# HeadphoneOut.net
KiCad netlist of a schematic drawn in EAGLE
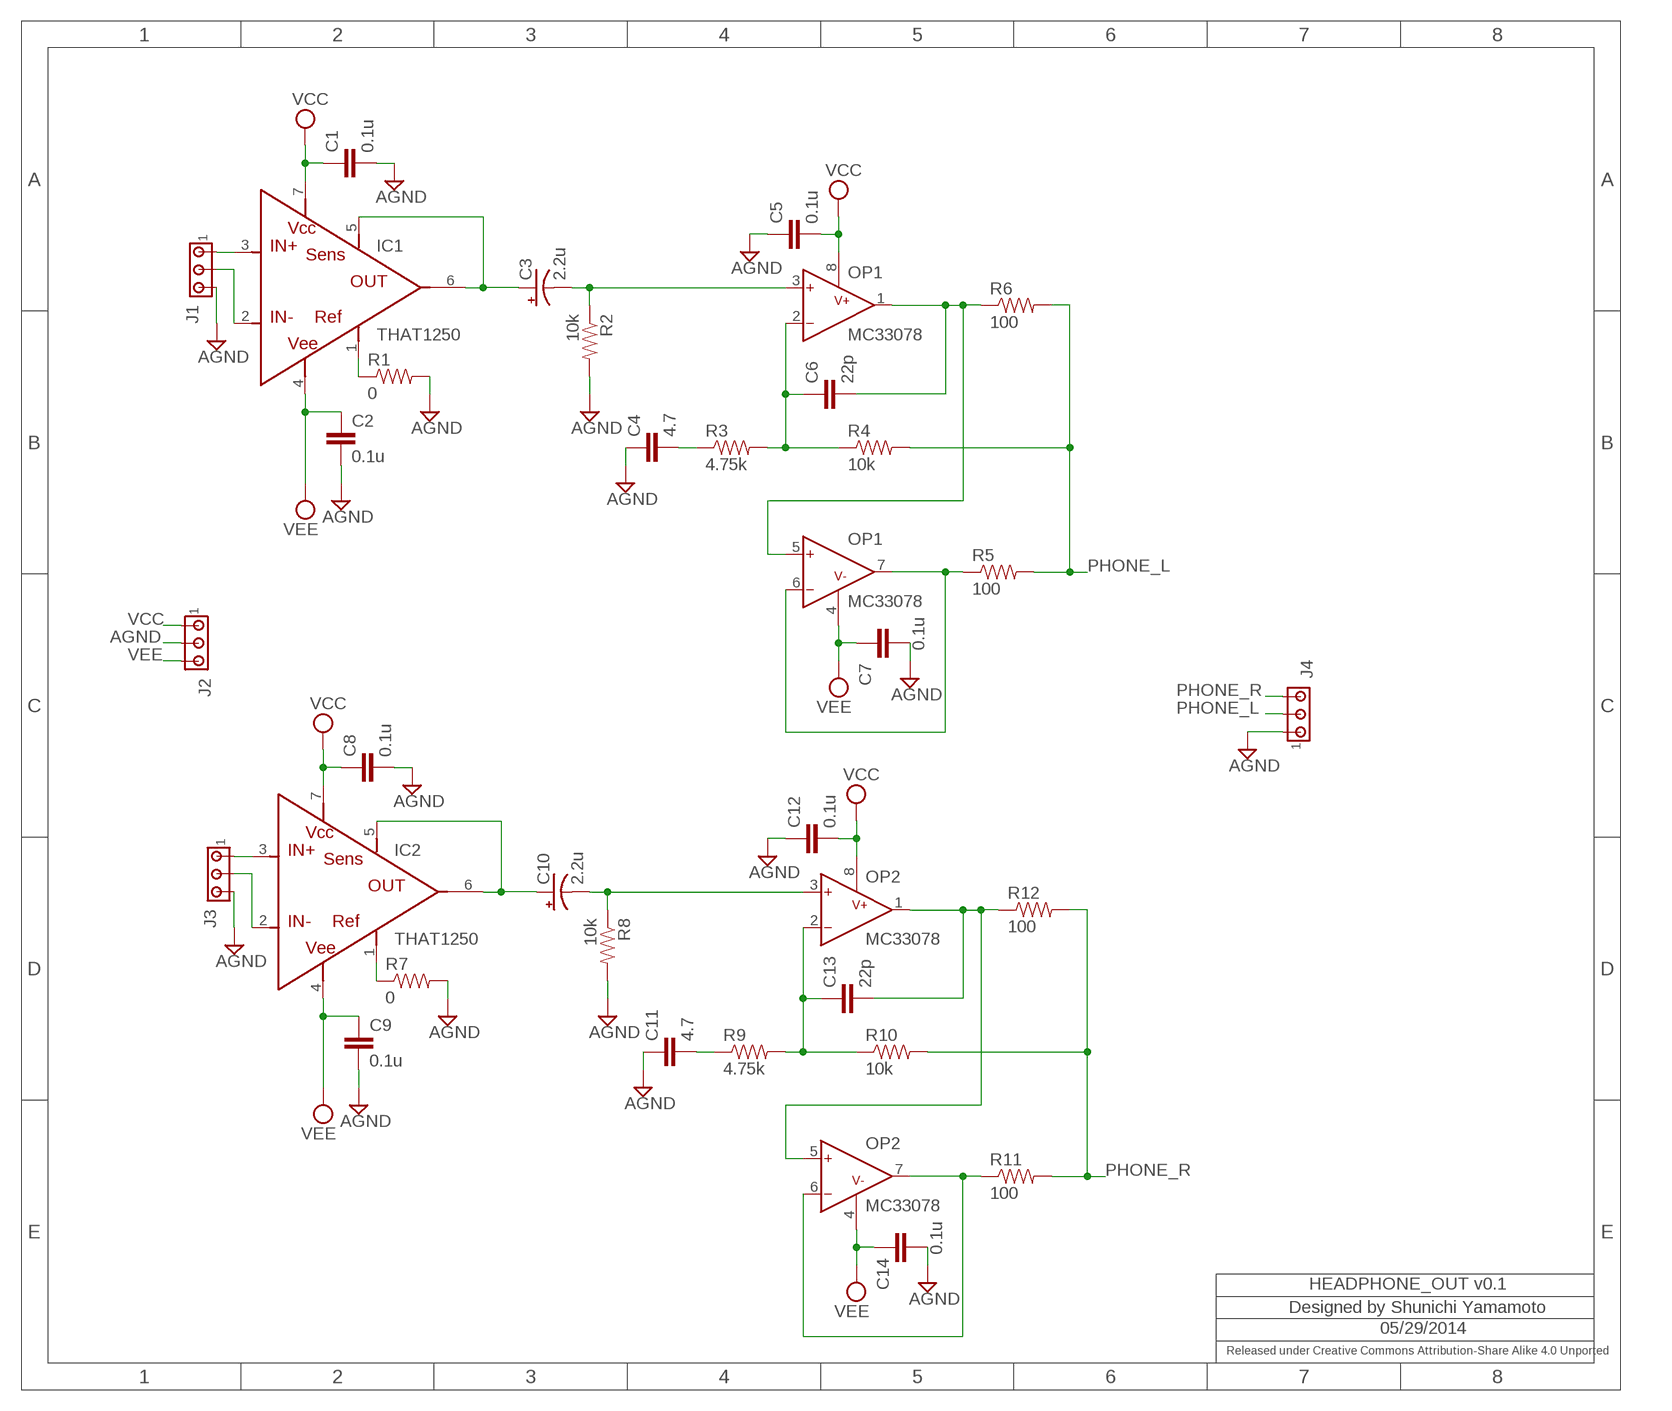
[diagram p0: schematic, sheet 1]

(export (version "E")
  (design (tool "Eeschema 10.0.6"))
  (components
    (comp (ref "C1")
      (value "0.1u")
      (footprint "eagle-import:C2012")
      (libsource (lib "eagle-import") (part "C-EUC2012"))
    )
    (comp (ref "C2")
      (value "0.1u")
      (footprint "eagle-import:C2012")
      (libsource (lib "eagle-import") (part "C-EUC2012"))
    )
    (comp (ref "C3")
      (value "2.2u")
      (footprint "eagle-import:UD-5X5,8_NICHICON")
      (libsource (lib "eagle-import") (part "CPOL-USUD-5X5,8"))
    )
    (comp (ref "C4")
      (value "4.7")
      (footprint "eagle-import:C2012")
      (libsource (lib "eagle-import") (part "C-EUC2012"))
    )
    (comp (ref "C5")
      (value "0.1u")
      (footprint "eagle-import:C2012")
      (libsource (lib "eagle-import") (part "C-EUC2012"))
    )
    (comp (ref "C6")
      (value "22p")
      (footprint "eagle-import:C2012")
      (libsource (lib "eagle-import") (part "C-EUC2012"))
    )
    (comp (ref "C7")
      (value "0.1u")
      (footprint "eagle-import:C2012")
      (libsource (lib "eagle-import") (part "C-EUC2012"))
    )
    (comp (ref "C8")
      (value "0.1u")
      (footprint "eagle-import:C2012")
      (libsource (lib "eagle-import") (part "C-EUC2012"))
    )
    (comp (ref "C9")
      (value "0.1u")
      (footprint "eagle-import:C2012")
      (libsource (lib "eagle-import") (part "C-EUC2012"))
    )
    (comp (ref "C10")
      (value "2.2u")
      (footprint "eagle-import:UD-5X5,8_NICHICON")
      (libsource (lib "eagle-import") (part "CPOL-USUD-5X5,8"))
    )
    (comp (ref "C11")
      (value "4.7")
      (footprint "eagle-import:C2012")
      (libsource (lib "eagle-import") (part "C-EUC2012"))
    )
    (comp (ref "C12")
      (value "0.1u")
      (footprint "eagle-import:C2012")
      (libsource (lib "eagle-import") (part "C-EUC2012"))
    )
    (comp (ref "C13")
      (value "22p")
      (footprint "eagle-import:C2012")
      (libsource (lib "eagle-import") (part "C-EUC2012"))
    )
    (comp (ref "C14")
      (value "0.1u")
      (footprint "eagle-import:C2012")
      (libsource (lib "eagle-import") (part "C-EUC2012"))
    )
    (comp (ref "IC1")
      (value "THAT1250")
      (footprint "eagle-import:SOIC8")
      (libsource (lib "eagle-import") (part "THAT1250"))
    )
    (comp (ref "IC2")
      (value "THAT1250")
      (footprint "eagle-import:SOIC8")
      (libsource (lib "eagle-import") (part "THAT1250"))
    )
    (comp (ref "J1")
      (value "MTA03-100")
      (footprint "eagle-import:10X03MTA")
      (libsource (lib "eagle-import") (part "MTA03-100"))
    )
    (comp (ref "J2")
      (value "MTA03-156")
      (footprint "eagle-import:1X3MTA")
      (libsource (lib "eagle-import") (part "MTA03-156"))
    )
    (comp (ref "J3")
      (value "MTA03-100")
      (footprint "eagle-import:10X03MTA")
      (libsource (lib "eagle-import") (part "MTA03-100"))
    )
    (comp (ref "J4")
      (value "MTA03-100")
      (footprint "eagle-import:10X03MTA")
      (libsource (lib "eagle-import") (part "MTA03-100"))
    )
    (comp (ref "OP1")
      (value "MC33078")
      (footprint "eagle-import:SOIC8@1")
      (libsource (lib "eagle-import") (part "LME49860"))
    )
    (comp (ref "OP2")
      (value "MC33078")
      (footprint "eagle-import:SOIC8@1")
      (libsource (lib "eagle-import") (part "LME49860"))
    )
    (comp (ref "R1")
      (value "0")
      (footprint "eagle-import:0805")
      (libsource (lib "eagle-import") (part "RESISTOR0805-RES"))
    )
    (comp (ref "R2")
      (value "10k")
      (footprint "eagle-import:0805")
      (libsource (lib "eagle-import") (part "RESISTOR0805-RES"))
    )
    (comp (ref "R3")
      (value "4.75k")
      (footprint "eagle-import:0805")
      (libsource (lib "eagle-import") (part "RESISTOR0805-RES"))
    )
    (comp (ref "R4")
      (value "10k")
      (footprint "eagle-import:0805")
      (libsource (lib "eagle-import") (part "RESISTOR0805-RES"))
    )
    (comp (ref "R5")
      (value "100")
      (footprint "eagle-import:0805")
      (libsource (lib "eagle-import") (part "RESISTOR0805-RES"))
    )
    (comp (ref "R6")
      (value "100")
      (footprint "eagle-import:0805")
      (libsource (lib "eagle-import") (part "RESISTOR0805-RES"))
    )
    (comp (ref "R7")
      (value "0")
      (footprint "eagle-import:0805")
      (libsource (lib "eagle-import") (part "RESISTOR0805-RES"))
    )
    (comp (ref "R8")
      (value "10k")
      (footprint "eagle-import:0805")
      (libsource (lib "eagle-import") (part "RESISTOR0805-RES"))
    )
    (comp (ref "R9")
      (value "4.75k")
      (footprint "eagle-import:0805")
      (libsource (lib "eagle-import") (part "RESISTOR0805-RES"))
    )
    (comp (ref "R10")
      (value "10k")
      (footprint "eagle-import:0805")
      (libsource (lib "eagle-import") (part "RESISTOR0805-RES"))
    )
    (comp (ref "R11")
      (value "100")
      (footprint "eagle-import:0805")
      (libsource (lib "eagle-import") (part "RESISTOR0805-RES"))
    )
    (comp (ref "R12")
      (value "100")
      (footprint "eagle-import:0805")
      (libsource (lib "eagle-import") (part "RESISTOR0805-RES"))
    )
  )
  (nets
    (net (code "1") (name "/PHONE_L") (class "Default")
      (node (ref "J4") (pin "2") (pinfunction "2_2") (pintype "passive"))
      (node (ref "R4") (pin "2") (pinfunction "2_2") (pintype "passive"))
      (node (ref "R5") (pin "2") (pinfunction "2_2") (pintype "passive"))
      (node (ref "R6") (pin "2") (pinfunction "2_2") (pintype "passive"))
    )
    (net (code "2") (name "/PHONE_R") (class "Default")
      (node (ref "J4") (pin "3") (pinfunction "3_3") (pintype "passive"))
      (node (ref "R10") (pin "2") (pinfunction "2_2") (pintype "passive"))
      (node (ref "R11") (pin "2") (pinfunction "2_2") (pintype "passive"))
      (node (ref "R12") (pin "2") (pinfunction "2_2") (pintype "passive"))
    )
    (net (code "3") (name "AGND") (class "Default")
      (node (ref "C1") (pin "2") (pinfunction "2_2") (pintype "passive"))
      (node (ref "C11") (pin "1") (pinfunction "1_1") (pintype "passive"))
      (node (ref "C12") (pin "1") (pinfunction "1_1") (pintype "passive"))
      (node (ref "C14") (pin "2") (pinfunction "2_2") (pintype "passive"))
      (node (ref "C2") (pin "2") (pinfunction "2_2") (pintype "passive"))
      (node (ref "C4") (pin "1") (pinfunction "1_1") (pintype "passive"))
      (node (ref "C5") (pin "1") (pinfunction "1_1") (pintype "passive"))
      (node (ref "C7") (pin "2") (pinfunction "2_2") (pintype "passive"))
      (node (ref "C8") (pin "2") (pinfunction "2_2") (pintype "passive"))
      (node (ref "C9") (pin "2") (pinfunction "2_2") (pintype "passive"))
      (node (ref "J1") (pin "3") (pinfunction "3_3") (pintype "passive"))
      (node (ref "J2") (pin "2") (pinfunction "2_2") (pintype "passive"))
      (node (ref "J3") (pin "3") (pinfunction "3_3") (pintype "passive"))
      (node (ref "J4") (pin "1") (pinfunction "1_1") (pintype "passive"))
      (node (ref "R1") (pin "2") (pinfunction "2_2") (pintype "passive"))
      (node (ref "R2") (pin "2") (pinfunction "2_2") (pintype "passive"))
      (node (ref "R7") (pin "2") (pinfunction "2_2") (pintype "passive"))
      (node (ref "R8") (pin "2") (pinfunction "2_2") (pintype "passive"))
    )
    (net (code "4") (name "Net-(C4-Pad2)") (class "Default")
      (node (ref "C4") (pin "2") (pinfunction "2_2") (pintype "passive"))
      (node (ref "R3") (pin "1") (pinfunction "1_1") (pintype "passive"))
    )
    (net (code "5") (name "Net-(C11-Pad2)") (class "Default")
      (node (ref "C11") (pin "2") (pinfunction "2_2") (pintype "passive"))
      (node (ref "R9") (pin "1") (pinfunction "1_1") (pintype "passive"))
    )
    (net (code "6") (name "Net-(IC1-IN+)") (class "Default")
      (node (ref "IC1") (pin "3") (pinfunction "IN+_3") (pintype "input"))
      (node (ref "J1") (pin "1") (pinfunction "1_1") (pintype "passive"))
    )
    (net (code "7") (name "Net-(IC1-IN-)") (class "Default")
      (node (ref "IC1") (pin "2") (pinfunction "IN-_2") (pintype "input"))
      (node (ref "J1") (pin "2") (pinfunction "2_2") (pintype "passive"))
    )
    (net (code "8") (name "Net-(IC1-OUT)") (class "Default")
      (node (ref "C3") (pin "+") (pinfunction "+_+") (pintype "passive"))
      (node (ref "IC1") (pin "5") (pinfunction "SENS_5") (pintype "power_in"))
      (node (ref "IC1") (pin "6") (pinfunction "OUT_6") (pintype "output"))
    )
    (net (code "9") (name "Net-(IC1-REF)") (class "Default")
      (node (ref "IC1") (pin "1") (pinfunction "REF_1") (pintype "input"))
      (node (ref "R1") (pin "1") (pinfunction "1_1") (pintype "passive"))
    )
    (net (code "10") (name "Net-(IC2-IN+)") (class "Default")
      (node (ref "IC2") (pin "3") (pinfunction "IN+_3") (pintype "input"))
      (node (ref "J3") (pin "1") (pinfunction "1_1") (pintype "passive"))
    )
    (net (code "11") (name "Net-(IC2-IN-)") (class "Default")
      (node (ref "IC2") (pin "2") (pinfunction "IN-_2") (pintype "input"))
      (node (ref "J3") (pin "2") (pinfunction "2_2") (pintype "passive"))
    )
    (net (code "12") (name "Net-(IC2-OUT)") (class "Default")
      (node (ref "C10") (pin "+") (pinfunction "+_+") (pintype "passive"))
      (node (ref "IC2") (pin "5") (pinfunction "SENS_5") (pintype "power_in"))
      (node (ref "IC2") (pin "6") (pinfunction "OUT_6") (pintype "output"))
    )
    (net (code "13") (name "Net-(IC2-REF)") (class "Default")
      (node (ref "IC2") (pin "1") (pinfunction "REF_1") (pintype "input"))
      (node (ref "R7") (pin "1") (pinfunction "1_1") (pintype "passive"))
    )
    (net (code "14") (name "Net-(OP1A-INA+)") (class "Default")
      (node (ref "C3") (pin "-") (pinfunction "-_-") (pintype "passive"))
      (node (ref "OP1") (pin "3") (pinfunction "INA+_3") (pintype "input"))
      (node (ref "R2") (pin "1") (pinfunction "1_1") (pintype "passive"))
    )
    (net (code "15") (name "Net-(OP1A-INA-)") (class "Default")
      (node (ref "C6") (pin "1") (pinfunction "1_1") (pintype "passive"))
      (node (ref "OP1") (pin "2") (pinfunction "INA-_2") (pintype "input"))
      (node (ref "R3") (pin "2") (pinfunction "2_2") (pintype "passive"))
      (node (ref "R4") (pin "1") (pinfunction "1_1") (pintype "passive"))
    )
    (net (code "16") (name "Net-(OP1A-OUTA)") (class "Default")
      (node (ref "C6") (pin "2") (pinfunction "2_2") (pintype "passive"))
      (node (ref "OP1") (pin "1") (pinfunction "OUTA_1") (pintype "output"))
      (node (ref "OP1") (pin "5") (pinfunction "INB+_5") (pintype "input"))
      (node (ref "R6") (pin "1") (pinfunction "1_1") (pintype "passive"))
    )
    (net (code "17") (name "Net-(OP1B-INB-)") (class "Default")
      (node (ref "OP1") (pin "6") (pinfunction "INB-_6") (pintype "input"))
      (node (ref "OP1") (pin "7") (pinfunction "OUTB_7") (pintype "output"))
      (node (ref "R5") (pin "1") (pinfunction "1_1") (pintype "passive"))
    )
    (net (code "18") (name "Net-(OP2A-INA+)") (class "Default")
      (node (ref "C10") (pin "-") (pinfunction "-_-") (pintype "passive"))
      (node (ref "OP2") (pin "3") (pinfunction "INA+_3") (pintype "input"))
      (node (ref "R8") (pin "1") (pinfunction "1_1") (pintype "passive"))
    )
    (net (code "19") (name "Net-(OP2A-INA-)") (class "Default")
      (node (ref "C13") (pin "1") (pinfunction "1_1") (pintype "passive"))
      (node (ref "OP2") (pin "2") (pinfunction "INA-_2") (pintype "input"))
      (node (ref "R10") (pin "1") (pinfunction "1_1") (pintype "passive"))
      (node (ref "R9") (pin "2") (pinfunction "2_2") (pintype "passive"))
    )
    (net (code "20") (name "Net-(OP2A-OUTA)") (class "Default")
      (node (ref "C13") (pin "2") (pinfunction "2_2") (pintype "passive"))
      (node (ref "OP2") (pin "1") (pinfunction "OUTA_1") (pintype "output"))
      (node (ref "OP2") (pin "5") (pinfunction "INB+_5") (pintype "input"))
      (node (ref "R12") (pin "1") (pinfunction "1_1") (pintype "passive"))
    )
    (net (code "21") (name "Net-(OP2B-INB-)") (class "Default")
      (node (ref "OP2") (pin "6") (pinfunction "INB-_6") (pintype "input"))
      (node (ref "OP2") (pin "7") (pinfunction "OUTB_7") (pintype "output"))
      (node (ref "R11") (pin "1") (pinfunction "1_1") (pintype "passive"))
    )
    (net (code "22") (name "VCC") (class "Default")
      (node (ref "C1") (pin "1") (pinfunction "1_1") (pintype "passive"))
      (node (ref "C12") (pin "2") (pinfunction "2_2") (pintype "passive"))
      (node (ref "C5") (pin "2") (pinfunction "2_2") (pintype "passive"))
      (node (ref "C8") (pin "1") (pinfunction "1_1") (pintype "passive"))
      (node (ref "IC1") (pin "7") (pinfunction "VCC_7") (pintype "power_in"))
      (node (ref "IC2") (pin "7") (pinfunction "VCC_7") (pintype "power_in"))
      (node (ref "J2") (pin "1") (pinfunction "1_1") (pintype "passive"))
      (node (ref "OP1") (pin "8") (pinfunction "V+_8") (pintype "power_in"))
      (node (ref "OP2") (pin "8") (pinfunction "V+_8") (pintype "power_in"))
    )
    (net (code "23") (name "VEE") (class "Default")
      (node (ref "C14") (pin "1") (pinfunction "1_1") (pintype "passive"))
      (node (ref "C2") (pin "1") (pinfunction "1_1") (pintype "passive"))
      (node (ref "C7") (pin "1") (pinfunction "1_1") (pintype "passive"))
      (node (ref "C9") (pin "1") (pinfunction "1_1") (pintype "passive"))
      (node (ref "IC1") (pin "4") (pinfunction "VEE_4") (pintype "power_in"))
      (node (ref "IC2") (pin "4") (pinfunction "VEE_4") (pintype "power_in"))
      (node (ref "J2") (pin "3") (pinfunction "3_3") (pintype "passive"))
      (node (ref "OP1") (pin "4") (pinfunction "V-_4") (pintype "power_in"))
      (node (ref "OP2") (pin "4") (pinfunction "V-_4") (pintype "power_in"))
    )
  )
)
